# SCH_Arduino_Polo_R6_CAN_cluster_2022-01-.net
KiCad netlist of a schematic drawn in EasyEDA
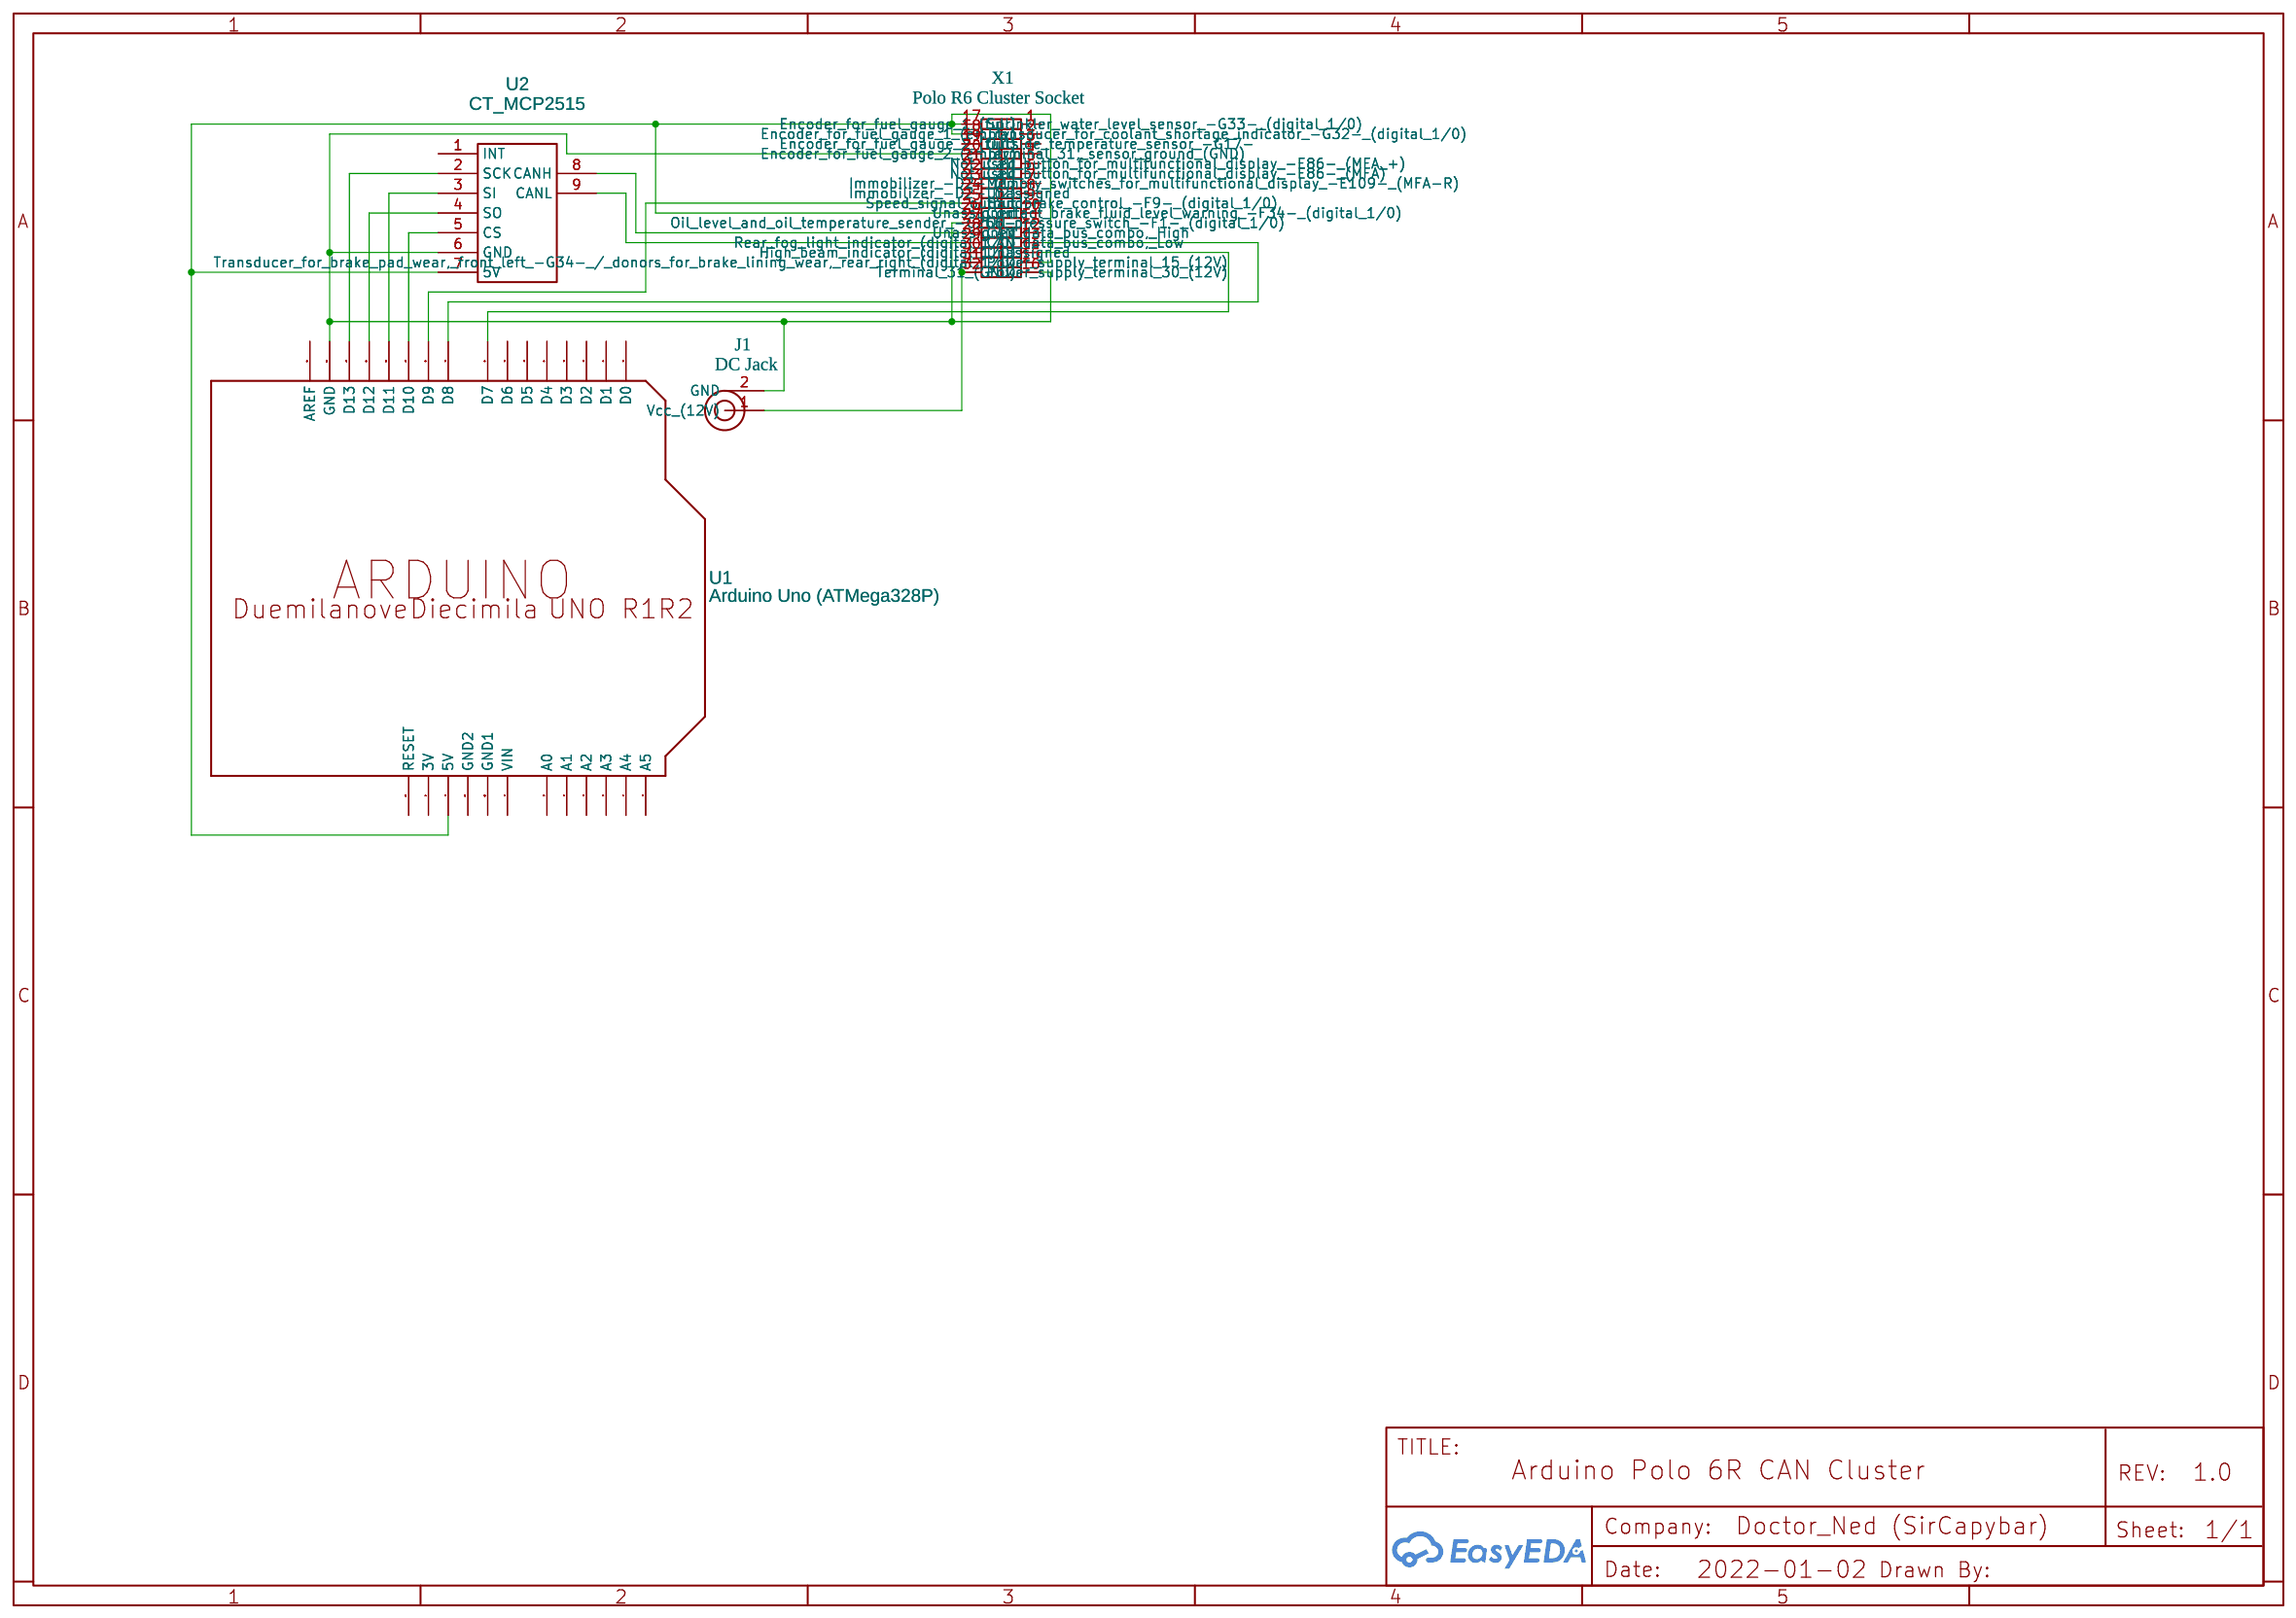
[diagram p0: schematic sheet]

(export (version "E")
  (design (tool "Eeschema 10.0.6"))
  (components
    (comp (ref "J1") (value "DC Jack") (libsource (lib "") (part "Unknown_370_-610")))
    (comp (ref "U1") (value "Arduino Uno (ATMega328P)") (libsource (lib "") (part "ARDUINOUNO")))
    (comp (ref "U2") (value "CT_MCP2515") (libsource (lib "") (part "CT_MCP2515")))
    (comp (ref "X1") (value "Polo R6 Cluster Socket") (libsource (lib "") (part "Unknown_560_-710")))
  )
  (nets
    (net (code "1") (name "Net-(J1-GND)") (class "Default")
      (node (ref "J1") (pin "2") (pinfunction "GND_2") (pintype "unspecified"))
      (node (ref "U1") (pin "GND") (pinfunction "GND_GND") (pintype "passive"))
      (node (ref "U2") (pin "6") (pinfunction "GND_6") (pintype "bidirectional"))
      (node (ref "X1") (pin "16") (pinfunction "Terminal_31_(GND)_16") (pintype "passive"))
      (node (ref "X1") (pin "20") (pinfunction "Terminal_31,_sensor_ground_(GND)_20") (pintype "passive"))
      (node (ref "X1") (pin "27") (pinfunction "Oil_pressure_switch_-F1-_(digital_1/0)_27") (pintype "input"))
    )
    (net (code "2") (name "Net-(J1-Vcc_(12V))") (class "Default")
      (node (ref "J1") (pin "1") (pinfunction "Vcc_(12V)_1") (pintype "unspecified"))
      (node (ref "X1") (pin "31") (pinfunction "Power_supply_terminal_15_(12V)_31") (pintype "passive"))
      (node (ref "X1") (pin "32") (pinfunction "Power_supply_terminal_30_(12V)_32") (pintype "passive"))
    )
    (net (code "3") (name "Net-(U2-5V)") (class "Default")
      (node (ref "U1") (pin "5V") (pinfunction "5V_5V") (pintype "passive"))
      (node (ref "U2") (pin "7") (pinfunction "5V_7") (pintype "bidirectional"))
      (node (ref "X1") (pin "15") (pinfunction "Transducer_for_brake_pad_wear,_front_left_-G34-_/_donors_for_brake_lining_wear,_rear_right_(digital_1/0)_15") (pintype "input"))
      (node (ref "X1") (pin "17") (pinfunction "Sprinkler_water_level_sensor_-G33-_(digital_1/0)_17") (pintype "input"))
      (node (ref "X1") (pin "18") (pinfunction "Transducer_for_coolant_shortage_indicator_-G32-_(digital_1/0)_18") (pintype "input"))
      (node (ref "X1") (pin "26") (pinfunction "Contact_brake_fluid_level_warning_-F34-_(digital_1/0)_26") (pintype "input"))
    )
    (net (code "4") (name "Net-(U2-CANH)") (class "Default")
      (node (ref "U2") (pin "8") (pinfunction "CANH_8") (pintype "bidirectional"))
      (node (ref "X1") (pin "28") (pinfunction "CAN_data_bus_combo,_High_28") (pintype "bidirectional"))
    )
    (net (code "5") (name "Net-(U2-CANL)") (class "Default")
      (node (ref "U2") (pin "9") (pinfunction "CANL_9") (pintype "bidirectional"))
      (node (ref "X1") (pin "29") (pinfunction "CAN_data_bus_combo,_Low_29") (pintype "bidirectional"))
    )
    (net (code "6") (name "Net-(U2-CS)") (class "Default")
      (node (ref "U1") (pin "D10") (pinfunction "D10_D10") (pintype "unspecified"))
      (node (ref "U2") (pin "5") (pinfunction "CS_5") (pintype "input"))
    )
    (net (code "7") (name "Net-(U2-SCK)") (class "Default")
      (node (ref "U1") (pin "D13") (pinfunction "D13_D13") (pintype "unspecified"))
      (node (ref "U2") (pin "2") (pinfunction "SCK_2") (pintype "input"))
    )
    (net (code "8") (name "Net-(U2-SI)") (class "Default")
      (node (ref "U1") (pin "D11") (pinfunction "D11_D11") (pintype "unspecified"))
      (node (ref "U2") (pin "3") (pinfunction "SI_3") (pintype "input"))
    )
    (net (code "9") (name "Net-(U2-SO)") (class "Default")
      (node (ref "U1") (pin "D12") (pinfunction "D12_D12") (pintype "unspecified"))
      (node (ref "U2") (pin "4") (pinfunction "SO_4") (pintype "output"))
    )
    (net (code "10") (name "Net-(X1-Handbrake_control_-F9-_(digital_1{slash}0))") (class "Default")
      (node (ref "U1") (pin "D9") (pinfunction "D9_D9") (pintype "unspecified"))
      (node (ref "X1") (pin "25") (pinfunction "Handbrake_control_-F9-_(digital_1/0)_25") (pintype "unspecified"))
    )
    (net (code "11") (name "Net-(X1-High_beam_indicator_(digital_1{slash}0))") (class "Default")
      (node (ref "U1") (pin "D7") (pinfunction "D7_D7") (pintype "unspecified"))
      (node (ref "X1") (pin "14") (pinfunction "High_beam_indicator_(digital_1/0)_14") (pintype "input"))
    )
    (net (code "12") (name "Net-(X1-Rear_fog_light_indicator_(digital_1{slash}0))") (class "Default")
      (node (ref "U1") (pin "D8") (pinfunction "D8_D8") (pintype "unspecified"))
      (node (ref "X1") (pin "13") (pinfunction "Rear_fog_light_indicator_(digital_1/0)_13") (pintype "input"))
    )
    (net (code "13") (name "unconnected-(U1-Pad3V)") (class "Default")
      (node (ref "U1") (pin "3V") (pinfunction "3V_3V") (pintype "passive"))
    )
    (net (code "14") (name "unconnected-(U1-PadA0)") (class "Default")
      (node (ref "U1") (pin "A0") (pinfunction "A0_A0") (pintype "unspecified"))
    )
    (net (code "15") (name "unconnected-(U1-PadA1)") (class "Default")
      (node (ref "U1") (pin "A1") (pinfunction "A1_A1") (pintype "unspecified"))
    )
    (net (code "16") (name "unconnected-(U1-PadA2)") (class "Default")
      (node (ref "U1") (pin "A2") (pinfunction "A2_A2") (pintype "unspecified"))
    )
    (net (code "17") (name "unconnected-(U1-PadA3)") (class "Default")
      (node (ref "U1") (pin "A3") (pinfunction "A3_A3") (pintype "unspecified"))
    )
    (net (code "18") (name "unconnected-(U1-PadA4)") (class "Default")
      (node (ref "U1") (pin "A4") (pinfunction "A4_A4") (pintype "unspecified"))
    )
    (net (code "19") (name "unconnected-(U1-PadA5)") (class "Default")
      (node (ref "U1") (pin "A5") (pinfunction "A5_A5") (pintype "unspecified"))
    )
    (net (code "20") (name "unconnected-(U1-PadAREF)") (class "Default")
      (node (ref "U1") (pin "AREF") (pinfunction "AREF_AREF") (pintype "unspecified"))
    )
    (net (code "21") (name "unconnected-(U1-PadD0)") (class "Default")
      (node (ref "U1") (pin "D0") (pinfunction "D0_D0") (pintype "unspecified"))
    )
    (net (code "22") (name "unconnected-(U1-PadD1)") (class "Default")
      (node (ref "U1") (pin "D1") (pinfunction "D1_D1") (pintype "unspecified"))
    )
    (net (code "23") (name "unconnected-(U1-PadD2)") (class "Default")
      (node (ref "U1") (pin "D2") (pinfunction "D2_D2") (pintype "unspecified"))
    )
    (net (code "24") (name "unconnected-(U1-PadD3)") (class "Default")
      (node (ref "U1") (pin "D3") (pinfunction "D3_D3") (pintype "unspecified"))
    )
    (net (code "25") (name "unconnected-(U1-PadD4)") (class "Default")
      (node (ref "U1") (pin "D4") (pinfunction "D4_D4") (pintype "unspecified"))
    )
    (net (code "26") (name "unconnected-(U1-PadD5)") (class "Default")
      (node (ref "U1") (pin "D5") (pinfunction "D5_D5") (pintype "unspecified"))
    )
    (net (code "27") (name "unconnected-(U1-PadD6)") (class "Default")
      (node (ref "U1") (pin "D6") (pinfunction "D6_D6") (pintype "unspecified"))
    )
    (net (code "28") (name "unconnected-(U1-PadGND1)") (class "Default")
      (node (ref "U1") (pin "GND1") (pinfunction "GND1_GND1") (pintype "passive"))
    )
    (net (code "29") (name "unconnected-(U1-PadGND2)") (class "Default")
      (node (ref "U1") (pin "GND2") (pinfunction "GND2_GND2") (pintype "passive"))
    )
    (net (code "30") (name "unconnected-(U1-PadRESET)") (class "Default")
      (node (ref "U1") (pin "RESET") (pinfunction "RESET_RESET") (pintype "unspecified"))
    )
    (net (code "31") (name "unconnected-(U1-PadVIN)") (class "Default")
      (node (ref "U1") (pin "VIN") (pinfunction "VIN_VIN") (pintype "passive"))
    )
    (net (code "32") (name "unconnected-(U2-INT-Pad1)") (class "Default")
      (node (ref "U2") (pin "1") (pinfunction "INT_1") (pintype "output"))
    )
    (net (code "33") (name "unconnected-(X1-Call_button_for_multifunctional_display_-E86-_(MFA)-Pad22)") (class "Default")
      (node (ref "X1") (pin "22") (pinfunction "Call_button_for_multifunctional_display_-E86-_(MFA)_22") (pintype "input"))
    )
    (net (code "34") (name "unconnected-(X1-Call_button_for_multifunctional_display_-E86-_(MFA_+)-Pad21)") (class "Default")
      (node (ref "X1") (pin "21") (pinfunction "Call_button_for_multifunctional_display_-E86-_(MFA_+)_21") (pintype "input"))
    )
    (net (code "35") (name "unconnected-(X1-Encoder_for_fuel_gauge_1_(empty)-Pad2)") (class "Default")
      (node (ref "X1") (pin "2") (pinfunction "Encoder_for_fuel_gauge_1_(empty)_2") (pintype "input"))
    )
    (net (code "36") (name "unconnected-(X1-Encoder_for_fuel_gauge_1_(full)-Pad1)") (class "Default")
      (node (ref "X1") (pin "1") (pinfunction "Encoder_for_fuel_gauge_1_(full)_1") (pintype "input"))
    )
    (net (code "37") (name "unconnected-(X1-Encoder_for_fuel_gauge_2_(empty)-Pad4)") (class "Default")
      (node (ref "X1") (pin "4") (pinfunction "Encoder_for_fuel_gauge_2_(empty)_4") (pintype "input"))
    )
    (net (code "38") (name "unconnected-(X1-Encoder_for_fuel_gauge_2_(full)-Pad3)") (class "Default")
      (node (ref "X1") (pin "3") (pinfunction "Encoder_for_fuel_gauge_2_(full)_3") (pintype "input"))
    )
    (net (code "39") (name "unconnected-(X1-Immobilizer_-D2-_(1)-Pad7)") (class "Default")
      (node (ref "X1") (pin "7") (pinfunction "Immobilizer_-D2-_(1)_7") (pintype "input"))
    )
    (net (code "40") (name "unconnected-(X1-Immobilizer_-D2-_(2)-Pad8)") (class "Default")
      (node (ref "X1") (pin "8") (pinfunction "Immobilizer_-D2-_(2)_8") (pintype "input"))
    )
    (net (code "41") (name "unconnected-(X1-Memory_switches_for_multifunctional_display_-E109-_(MFA-R)-Pad23)") (class "Default")
      (node (ref "X1") (pin "23") (pinfunction "Memory_switches_for_multifunctional_display_-E109-_(MFA-R)_23") (pintype "input"))
    )
    (net (code "42") (name "unconnected-(X1-Not_used-Pad5)") (class "Default")
      (node (ref "X1") (pin "5") (pinfunction "Not_used_5") (pintype "unspecified"))
    )
    (net (code "43") (name "unconnected-(X1-Not_used-Pad6)") (class "Default")
      (node (ref "X1") (pin "6") (pinfunction "Not_used_6") (pintype "unspecified"))
    )
    (net (code "44") (name "unconnected-(X1-Oil_level_and_oil_temperature_sender_-G266--Pad11)") (class "Default")
      (node (ref "X1") (pin "11") (pinfunction "Oil_level_and_oil_temperature_sender_-G266-_11") (pintype "input"))
    )
    (net (code "45") (name "unconnected-(X1-Outside_temperature_sensor_-G17--Pad19)") (class "Default")
      (node (ref "X1") (pin "19") (pinfunction "Outside_temperature_sensor_-G17-_19") (pintype "input"))
    )
    (net (code "46") (name "unconnected-(X1-Speed_signal_output-Pad9)") (class "Default")
      (node (ref "X1") (pin "9") (pinfunction "Speed_signal_output_9") (pintype "output"))
    )
    (net (code "47") (name "unconnected-(X1-Unassigned-Pad10)") (class "Default")
      (node (ref "X1") (pin "10") (pinfunction "Unassigned_10") (pintype "unspecified"))
    )
    (net (code "48") (name "unconnected-(X1-Unassigned-Pad12)") (class "Default")
      (node (ref "X1") (pin "12") (pinfunction "Unassigned_12") (pintype "unspecified"))
    )
    (net (code "49") (name "unconnected-(X1-Unassigned-Pad24)") (class "Default")
      (node (ref "X1") (pin "24") (pinfunction "Unassigned_24") (pintype "unspecified"))
    )
    (net (code "50") (name "unconnected-(X1-Unassigned-Pad30)") (class "Default")
      (node (ref "X1") (pin "30") (pinfunction "Unassigned_30") (pintype "unspecified"))
    )
  )
)
